# Power.net
KiCad netlist of a schematic drawn in Altium Designer
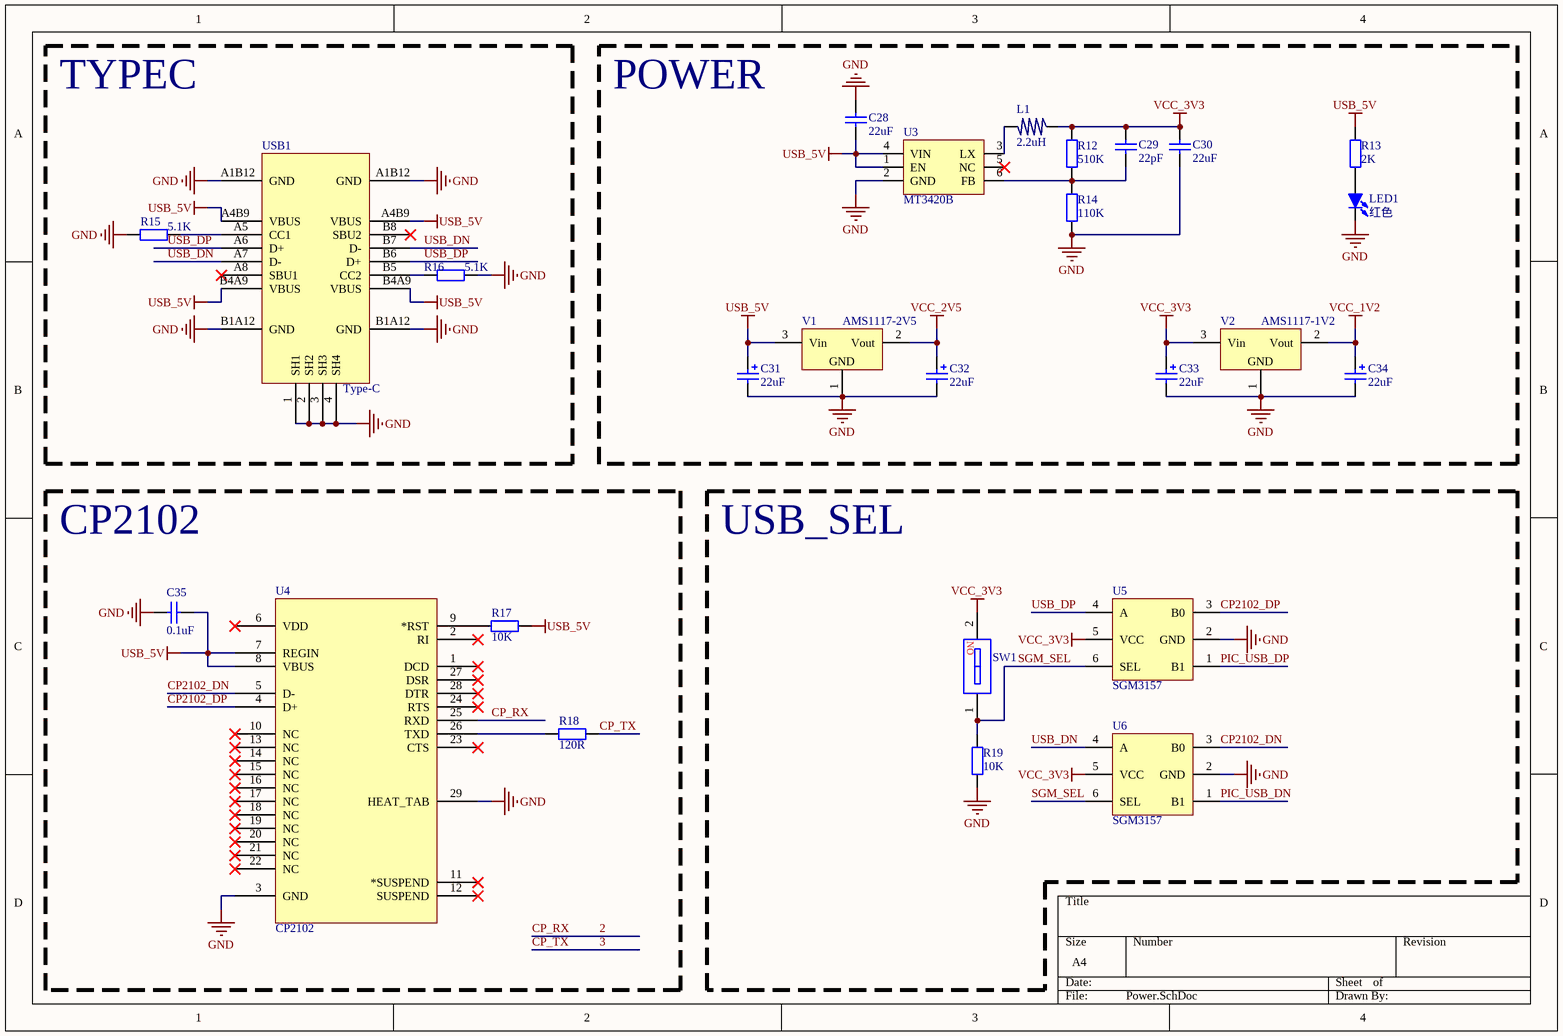
[diagram p0: Power.SchDoc]

(export (version "E")
  (design (tool "Eeschema 10.0.6"))
  (components
    (comp (ref "C28")
      (value "22uF")
      (footprint "0603_C _MINI")
      (description "贴片电容")
      (libsource (lib "My_Devices") (part "0603_C_MINI"))
    )
    (comp (ref "C29")
      (value "22pF")
      (footprint "0402_C")
      (description "贴片电容")
      (libsource (lib "My_Devices") (part "0402_C"))
    )
    (comp (ref "C30")
      (value "22uF")
      (footprint "0603_C _MINI")
      (description "贴片电容")
      (libsource (lib "My_Devices") (part "0603_C_MINI"))
    )
    (comp (ref "C31")
      (value "22uF")
      (footprint "CASE-A_3216")
      (description "贴片钽电容")
      (libsource (lib "My_Devices") (part "3216_C"))
    )
    (comp (ref "C32")
      (value "22uF")
      (footprint "CASE-A_3216")
      (description "贴片钽电容")
      (libsource (lib "My_Devices") (part "3216_C"))
    )
    (comp (ref "C33")
      (value "22uF")
      (footprint "CASE-A_3216")
      (description "贴片钽电容")
      (libsource (lib "My_Devices") (part "3216_C"))
    )
    (comp (ref "C34")
      (value "22uF")
      (footprint "CASE-A_3216")
      (description "贴片钽电容")
      (libsource (lib "My_Devices") (part "3216_C"))
    )
    (comp (ref "C35")
      (value "0.1uF")
      (footprint "0402_C")
      (description "贴片电容")
      (libsource (lib "My_Devices") (part "0402_C"))
    )
    (comp (ref "L1") (value "2.2uH") (footprint "NR3015") (libsource (lib "Schlib1") (part "L")))
    (comp (ref "LED1")
      (value "红色")
      (footprint "LED 0603R")
      (description "贴片LED")
      (fields (field (name "版权归属") "源创客"))
      (libsource (lib "My_Devices") (part "0603_LED_R"))
    )
    (comp (ref "R12")
      (value "510K")
      (footprint "0402_R")
      (description "贴片电阻")
      (libsource (lib "") (part "0402_R_1"))
    )
    (comp (ref "R13")
      (value "2K")
      (footprint "0402_R")
      (description "贴片电阻")
      (libsource (lib "") (part "0402_R_1"))
    )
    (comp (ref "R14")
      (value "110K")
      (footprint "0402_R")
      (description "贴片电阻")
      (libsource (lib "") (part "0402_R_1"))
    )
    (comp (ref "R15")
      (value "5.1K")
      (footprint "0402_R")
      (description "贴片电阻")
      (libsource (lib "My_Devices") (part "0402_R"))
    )
    (comp (ref "R16")
      (value "5.1K")
      (footprint "0402_R")
      (description "贴片电阻")
      (libsource (lib "My_Devices") (part "0402_R"))
    )
    (comp (ref "R17")
      (value "10K")
      (footprint "0402_R")
      (description "贴片电阻")
      (libsource (lib "My_Devices") (part "0402_R"))
    )
    (comp (ref "R18")
      (value "120R")
      (footprint "0402_R")
      (description "贴片电阻")
      (libsource (lib "My_Devices") (part "0402_R"))
    )
    (comp (ref "R19")
      (value "10K")
      (footprint "0402_R")
      (description "贴片电阻")
      (libsource (lib "") (part "0402_R_1"))
    )
    (comp (ref "SW1")
      (value "CSW-1P")
      (footprint "SW-SMD_DSIC01LSGET")
      (description "1路编码开关")
      (fields (field (name "版权归属") "源创客"))
      (libsource (lib "My_Devices") (part "CSW-1P"))
    )
    (comp (ref "U3")
      (value "MT3420B")
      (footprint "SOT23-6L")
      (description "DCDC")
      (libsource (lib "Schlib1") (part "MT3420B"))
    )
    (comp (ref "U4")
      (value "CP2102")
      (footprint "QFN28 5x5_N")
      (description "USB转TTL")
      (libsource (lib "My_Devices") (part "CP2102"))
    )
    (comp (ref "U5")
      (value "SGM3157")
      (footprint "SC-70-6_L2.2-W1.3-P0.65-LS2.2-BR")
      (description "模拟开关")
      (libsource (lib "Schlib1") (part "SGM3157"))
    )
    (comp (ref "U6")
      (value "SGM3157")
      (footprint "SC-70-6_L2.2-W1.3-P0.65-LS2.2-BR")
      (description "模拟开关")
      (libsource (lib "Schlib1") (part "SGM3157"))
    )
    (comp (ref "USB1")
      (value "Type-C")
      (footprint "Type-C-TOP")
      (libsource (lib "My_Devices") (part "USB-Type-C-TOP"))
    )
    (comp (ref "V1")
      (value "AMS1117-2V5")
      (footprint "SOT89_N")
      (description "三端稳压芯片")
      (fields (field (name "版权归属") "源创客"))
      (libsource (lib "My_Devices") (part "AMS1117"))
    )
    (comp (ref "V2")
      (value "AMS1117-1V2")
      (footprint "SOT89_N")
      (description "三端稳压芯片")
      (fields (field (name "版权归属") "源创客"))
      (libsource (lib "My_Devices") (part "AMS1117"))
    )
  )
  (nets
    (net (code "1") (name "/2") (class "Default")
      (node (ref "U4") (pin "25") (pinfunction "RXD_25") (pintype "passive"))
    )
    (net (code "2") (name "/3") (class "Default")
      (node (ref "R18") (pin "2") (pinfunction "2_2") (pintype "passive"))
    )
    (net (code "3") (name "/CP2102_DN") (class "Default")
      (node (ref "U4") (pin "5") (pinfunction "D-_5") (pintype "passive"))
      (node (ref "U6") (pin "3") (pinfunction "B0_3") (pintype "passive"))
    )
    (net (code "4") (name "/CP2102_DP") (class "Default")
      (node (ref "U4") (pin "4") (pinfunction "D+_4") (pintype "passive"))
      (node (ref "U5") (pin "3") (pinfunction "B0_3") (pintype "passive"))
    )
    (net (code "5") (name "/PIC_USB_DN") (class "Default")
      (node (ref "U6") (pin "1") (pinfunction "B1_1") (pintype "passive"))
    )
    (net (code "6") (name "/PIC_USB_DP") (class "Default")
      (node (ref "U5") (pin "1") (pinfunction "B1_1") (pintype "passive"))
    )
    (net (code "7") (name "/SGM_SEL") (class "Default")
      (node (ref "R19") (pin "2") (pinfunction "2_2") (pintype "passive"))
      (node (ref "SW1") (pin "1") (pinfunction "1_1") (pintype "passive"))
      (node (ref "U5") (pin "6") (pinfunction "SEL_6") (pintype "passive"))
      (node (ref "U6") (pin "6") (pinfunction "SEL_6") (pintype "passive"))
    )
    (net (code "8") (name "/USB_DN") (class "Default")
      (node (ref "U6") (pin "4") (pinfunction "A_4") (pintype "passive"))
      (node (ref "USB1") (pin "A7") (pinfunction "D-_A7") (pintype "passive"))
      (node (ref "USB1") (pin "B7") (pinfunction "D-_B7") (pintype "passive"))
    )
    (net (code "9") (name "/USB_DP") (class "Default")
      (node (ref "U5") (pin "4") (pinfunction "A_4") (pintype "passive"))
      (node (ref "USB1") (pin "A6") (pinfunction "D+_A6") (pintype "passive"))
      (node (ref "USB1") (pin "B6") (pinfunction "D+_B6") (pintype "passive"))
    )
    (net (code "10") (name "GND") (class "Default")
      (node (ref "C28") (pin "2") (pinfunction "2_2") (pintype "passive"))
      (node (ref "C30") (pin "1") (pinfunction "1_1") (pintype "passive"))
      (node (ref "C31") (pin "2") (pinfunction "2_2") (pintype "passive"))
      (node (ref "C32") (pin "2") (pinfunction "2_2") (pintype "passive"))
      (node (ref "C33") (pin "2") (pinfunction "2_2") (pintype "passive"))
      (node (ref "C34") (pin "2") (pinfunction "2_2") (pintype "passive"))
      (node (ref "C35") (pin "2") (pinfunction "2_2") (pintype "passive"))
      (node (ref "LED1") (pin "2") (pinfunction "K_2") (pintype "passive"))
      (node (ref "R14") (pin "1") (pinfunction "1_1") (pintype "passive"))
      (node (ref "R15") (pin "1") (pinfunction "1_1") (pintype "passive"))
      (node (ref "R16") (pin "2") (pinfunction "2_2") (pintype "passive"))
      (node (ref "R19") (pin "1") (pinfunction "1_1") (pintype "passive"))
      (node (ref "U3") (pin "2") (pinfunction "GND_2") (pintype "passive"))
      (node (ref "U4") (pin "29") (pinfunction "HEAT_TAB_29") (pintype "passive"))
      (node (ref "U4") (pin "3") (pinfunction "GND_3") (pintype "passive"))
      (node (ref "U5") (pin "2") (pinfunction "GND_2") (pintype "passive"))
      (node (ref "U6") (pin "2") (pinfunction "GND_2") (pintype "passive"))
      (node (ref "USB1") (pin "1") (pinfunction "SH1_1") (pintype "passive"))
      (node (ref "USB1") (pin "2") (pinfunction "SH2_2") (pintype "passive"))
      (node (ref "USB1") (pin "3") (pinfunction "SH3_3") (pintype "passive"))
      (node (ref "USB1") (pin "4") (pinfunction "SH4_4") (pintype "passive"))
      (node (ref "USB1") (pin "A1B12") (pinfunction "GND_A1B12") (pintype "passive"))
      (node (ref "USB1") (pin "B1A12") (pinfunction "GND_B1A12") (pintype "passive"))
      (node (ref "V1") (pin "1") (pinfunction "GND_1") (pintype "passive"))
      (node (ref "V2") (pin "1") (pinfunction "GND_1") (pintype "passive"))
    )
    (net (code "11") (name "Net-(LED1-A)") (class "Default")
      (node (ref "LED1") (pin "1") (pinfunction "A_1") (pintype "passive"))
      (node (ref "R13") (pin "1") (pinfunction "1_1") (pintype "passive"))
    )
    (net (code "12") (name "Net-(U3-FB)") (class "Default")
      (node (ref "C29") (pin "1") (pinfunction "1_1") (pintype "passive"))
      (node (ref "R12") (pin "1") (pinfunction "1_1") (pintype "passive"))
      (node (ref "R14") (pin "2") (pinfunction "2_2") (pintype "passive"))
      (node (ref "U3") (pin "6") (pinfunction "FB_6") (pintype "passive"))
    )
    (net (code "13") (name "Net-(U3-LX)") (class "Default")
      (node (ref "L1") (pin "2") (pintype "passive"))
      (node (ref "U3") (pin "3") (pinfunction "LX_3") (pintype "passive"))
    )
    (net (code "14") (name "Net-(U4-*RST)") (class "Default")
      (node (ref "R17") (pin "1") (pinfunction "1_1") (pintype "passive"))
      (node (ref "U4") (pin "9") (pinfunction "*RST_9") (pintype "passive"))
    )
    (net (code "15") (name "Net-(U4-TXD)") (class "Default")
      (node (ref "R18") (pin "1") (pinfunction "1_1") (pintype "passive"))
      (node (ref "U4") (pin "26") (pinfunction "TXD_26") (pintype "passive"))
    )
    (net (code "16") (name "Net-(USB1-CC1)") (class "Default")
      (node (ref "R15") (pin "2") (pinfunction "2_2") (pintype "passive"))
      (node (ref "USB1") (pin "A5") (pinfunction "CC1_A5") (pintype "passive"))
    )
    (net (code "17") (name "Net-(USB1-CC2)") (class "Default")
      (node (ref "R16") (pin "1") (pinfunction "1_1") (pintype "passive"))
      (node (ref "USB1") (pin "B5") (pinfunction "CC2_B5") (pintype "passive"))
    )
    (net (code "18") (name "USB_5V") (class "Default")
      (node (ref "C28") (pin "1") (pinfunction "1_1") (pintype "passive"))
      (node (ref "C31") (pin "1") (pinfunction "1_1") (pintype "passive"))
      (node (ref "C35") (pin "1") (pinfunction "1_1") (pintype "passive"))
      (node (ref "R13") (pin "2") (pinfunction "2_2") (pintype "passive"))
      (node (ref "R17") (pin "2") (pinfunction "2_2") (pintype "passive"))
      (node (ref "U3") (pin "1") (pinfunction "EN_1") (pintype "passive"))
      (node (ref "U3") (pin "4") (pinfunction "VIN_4") (pintype "passive"))
      (node (ref "U4") (pin "7") (pinfunction "REGIN_7") (pintype "passive"))
      (node (ref "U4") (pin "8") (pinfunction "VBUS_8") (pintype "passive"))
      (node (ref "USB1") (pin "A4B9") (pinfunction "VBUS_A4B9") (pintype "passive"))
      (node (ref "USB1") (pin "B4A9") (pinfunction "VBUS_B4A9") (pintype "passive"))
      (node (ref "V1") (pin "3") (pinfunction "Vin_3") (pintype "passive"))
    )
    (net (code "19") (name "VCC_1V2") (class "Default")
      (node (ref "C34") (pin "1") (pinfunction "1_1") (pintype "passive"))
      (node (ref "V2") (pin "2") (pinfunction "Vout_2") (pintype "passive"))
    )
    (net (code "20") (name "VCC_2V5") (class "Default")
      (node (ref "C32") (pin "1") (pinfunction "1_1") (pintype "passive"))
      (node (ref "V1") (pin "2") (pinfunction "Vout_2") (pintype "passive"))
    )
    (net (code "21") (name "VCC_3V3") (class "Default")
      (node (ref "C29") (pin "2") (pinfunction "2_2") (pintype "passive"))
      (node (ref "C30") (pin "2") (pinfunction "2_2") (pintype "passive"))
      (node (ref "C33") (pin "1") (pinfunction "1_1") (pintype "passive"))
      (node (ref "L1") (pin "1") (pintype "passive"))
      (node (ref "R12") (pin "2") (pinfunction "2_2") (pintype "passive"))
      (node (ref "SW1") (pin "2") (pinfunction "2_2") (pintype "passive"))
      (node (ref "U5") (pin "5") (pinfunction "VCC_5") (pintype "passive"))
      (node (ref "U6") (pin "5") (pinfunction "VCC_5") (pintype "passive"))
      (node (ref "V2") (pin "3") (pinfunction "Vin_3") (pintype "passive"))
    )
    (net (code "22") (name "unconnected-(U3-NC-Pad5)") (class "Default")
      (node (ref "U3") (pin "5") (pinfunction "NC_5") (pintype "passive+no_connect"))
    )
    (net (code "23") (name "unconnected-(U4-*SUSPEND-Pad11)") (class "Default")
      (node (ref "U4") (pin "11") (pinfunction "*SUSPEND_11") (pintype "passive+no_connect"))
    )
    (net (code "24") (name "unconnected-(U4-CTS-Pad23)") (class "Default")
      (node (ref "U4") (pin "23") (pinfunction "CTS_23") (pintype "passive+no_connect"))
    )
    (net (code "25") (name "unconnected-(U4-DCD-Pad1)") (class "Default")
      (node (ref "U4") (pin "1") (pinfunction "DCD_1") (pintype "passive+no_connect"))
    )
    (net (code "26") (name "unconnected-(U4-DSR-Pad27)") (class "Default")
      (node (ref "U4") (pin "27") (pinfunction "DSR_27") (pintype "passive+no_connect"))
    )
    (net (code "27") (name "unconnected-(U4-DTR-Pad28)") (class "Default")
      (node (ref "U4") (pin "28") (pinfunction "DTR_28") (pintype "passive+no_connect"))
    )
    (net (code "28") (name "unconnected-(U4-NC-Pad10)") (class "Default")
      (node (ref "U4") (pin "10") (pinfunction "NC_10") (pintype "passive+no_connect"))
    )
    (net (code "29") (name "unconnected-(U4-NC-Pad13)") (class "Default")
      (node (ref "U4") (pin "13") (pinfunction "NC_13") (pintype "passive+no_connect"))
    )
    (net (code "30") (name "unconnected-(U4-NC-Pad14)") (class "Default")
      (node (ref "U4") (pin "14") (pinfunction "NC_14") (pintype "passive+no_connect"))
    )
    (net (code "31") (name "unconnected-(U4-NC-Pad15)") (class "Default")
      (node (ref "U4") (pin "15") (pinfunction "NC_15") (pintype "passive+no_connect"))
    )
    (net (code "32") (name "unconnected-(U4-NC-Pad16)") (class "Default")
      (node (ref "U4") (pin "16") (pinfunction "NC_16") (pintype "passive+no_connect"))
    )
    (net (code "33") (name "unconnected-(U4-NC-Pad17)") (class "Default")
      (node (ref "U4") (pin "17") (pinfunction "NC_17") (pintype "passive+no_connect"))
    )
    (net (code "34") (name "unconnected-(U4-NC-Pad18)") (class "Default")
      (node (ref "U4") (pin "18") (pinfunction "NC_18") (pintype "passive+no_connect"))
    )
    (net (code "35") (name "unconnected-(U4-NC-Pad19)") (class "Default")
      (node (ref "U4") (pin "19") (pinfunction "NC_19") (pintype "passive+no_connect"))
    )
    (net (code "36") (name "unconnected-(U4-NC-Pad20)") (class "Default")
      (node (ref "U4") (pin "20") (pinfunction "NC_20") (pintype "passive+no_connect"))
    )
    (net (code "37") (name "unconnected-(U4-NC-Pad21)") (class "Default")
      (node (ref "U4") (pin "21") (pinfunction "NC_21") (pintype "passive+no_connect"))
    )
    (net (code "38") (name "unconnected-(U4-NC-Pad22)") (class "Default")
      (node (ref "U4") (pin "22") (pinfunction "NC_22") (pintype "passive+no_connect"))
    )
    (net (code "39") (name "unconnected-(U4-RI-Pad2)") (class "Default")
      (node (ref "U4") (pin "2") (pinfunction "RI_2") (pintype "passive+no_connect"))
    )
    (net (code "40") (name "unconnected-(U4-RTS-Pad24)") (class "Default")
      (node (ref "U4") (pin "24") (pinfunction "RTS_24") (pintype "passive+no_connect"))
    )
    (net (code "41") (name "unconnected-(U4-SUSPEND-Pad12)") (class "Default")
      (node (ref "U4") (pin "12") (pinfunction "SUSPEND_12") (pintype "passive+no_connect"))
    )
    (net (code "42") (name "unconnected-(U4-VDD-Pad6)") (class "Default")
      (node (ref "U4") (pin "6") (pinfunction "VDD_6") (pintype "passive+no_connect"))
    )
    (net (code "43") (name "unconnected-(USB1-SBU1-PadA8)") (class "Default")
      (node (ref "USB1") (pin "A8") (pinfunction "SBU1_A8") (pintype "passive+no_connect"))
    )
    (net (code "44") (name "unconnected-(USB1-SBU2-PadB8)") (class "Default")
      (node (ref "USB1") (pin "B8") (pinfunction "SBU2_B8") (pintype "passive+no_connect"))
    )
  )
)
